# NodeBoard.net
KiCad netlist of a schematic drawn in EAGLE
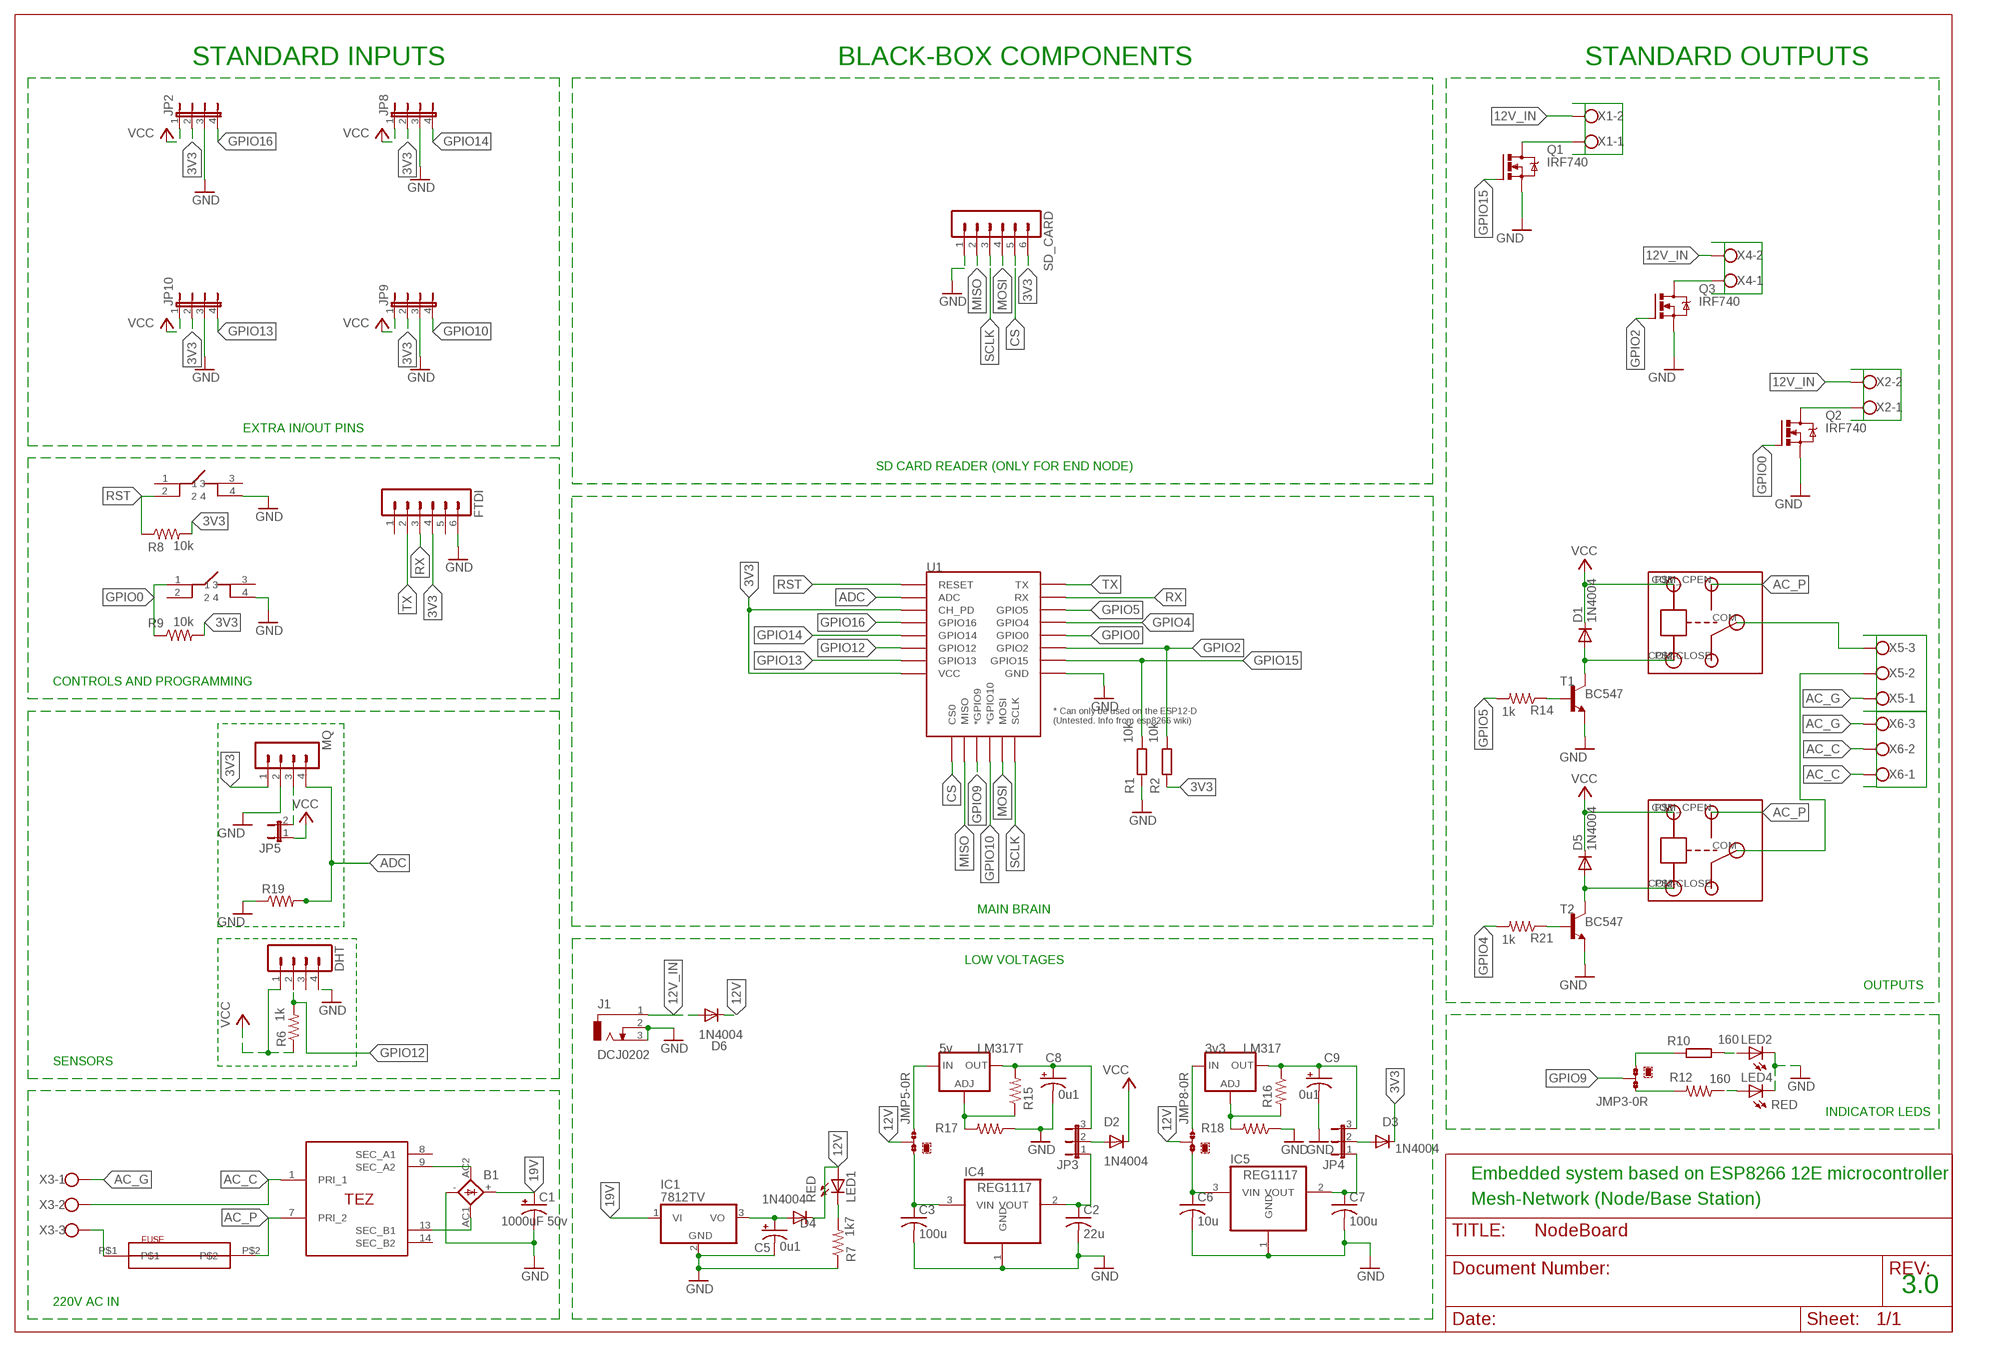
[diagram p0: schematic, sheet 1]

(export (version "E")
  (design (tool "Eeschema 10.0.6"))
  (components
    (comp (ref "B1")
      (value "KBL")
      (footprint "eagle-import:KBL")
      (libsource (lib "eagle-import") (part "KBL"))
    )
    (comp (ref "C1")
      (value "1000uF 50v")
      (footprint "eagle-import:E5-13")
      (libsource (lib "eagle-import") (part "CPOL-USE5-13"))
    )
    (comp (ref "C2")
      (value "22u")
      (footprint "eagle-import:C0805")
      (libsource (lib "eagle-import") (part "C-USC0805"))
    )
    (comp (ref "C3")
      (value "100u")
      (footprint "eagle-import:C0805")
      (libsource (lib "eagle-import") (part "C-USC0805"))
    )
    (comp (ref "C5")
      (value "0u1")
      (footprint "eagle-import:E2,5-6E")
      (libsource (lib "eagle-import") (part "resistor_CPOL-USE2,5-6E"))
    )
    (comp (ref "C6")
      (value "10u")
      (footprint "eagle-import:C0805")
      (libsource (lib "eagle-import") (part "C-USC0805"))
    )
    (comp (ref "C7")
      (value "100u")
      (footprint "eagle-import:C0805")
      (libsource (lib "eagle-import") (part "C-USC0805"))
    )
    (comp (ref "C8")
      (value "0u1")
      (footprint "eagle-import:E2,5-6E")
      (libsource (lib "eagle-import") (part "resistor_CPOL-USE2,5-6E"))
    )
    (comp (ref "C9")
      (value "0u1")
      (footprint "eagle-import:E2,5-6E")
      (libsource (lib "eagle-import") (part "resistor_CPOL-USE2,5-6E"))
    )
    (comp (ref "D1")
      (value "1N4004")
      (footprint "eagle-import:DO41-10")
      (libsource (lib "eagle-import") (part "1N4004"))
    )
    (comp (ref "D2")
      (value "1N4004")
      (footprint "eagle-import:DO41-10")
      (libsource (lib "eagle-import") (part "1N4004"))
    )
    (comp (ref "D3")
      (value "1N4004")
      (footprint "eagle-import:DO41-10")
      (libsource (lib "eagle-import") (part "1N4004"))
    )
    (comp (ref "D4")
      (value "1N4004")
      (footprint "eagle-import:DO41-10")
      (libsource (lib "eagle-import") (part "1N4004"))
    )
    (comp (ref "D5")
      (value "1N4004")
      (footprint "eagle-import:DO41-10")
      (libsource (lib "eagle-import") (part "1N4004"))
    )
    (comp (ref "D6")
      (value "1N4004")
      (footprint "eagle-import:DO41-10")
      (libsource (lib "eagle-import") (part "1N4004"))
    )
    (comp (ref "DHT")
      (value "MA04-1")
      (footprint "eagle-import:MA04-1")
      (libsource (lib "eagle-import") (part "MA04-1"))
    )
    (comp (ref "FTDI")
      (value "MA06-1")
      (footprint "eagle-import:MA06-1")
      (libsource (lib "eagle-import") (part "MA06-1"))
    )
    (comp (ref "IC1")
      (value "7812TV")
      (footprint "eagle-import:TO220V")
      (libsource (lib "eagle-import") (part "78TV12"))
    )
    (comp (ref "IC4")
      (value "REG1117")
      (footprint "eagle-import:SOT223")
      (libsource (lib "eagle-import") (part "REG1117"))
    )
    (comp (ref "IC5")
      (value "REG1117")
      (footprint "eagle-import:SOT223")
      (libsource (lib "eagle-import") (part "REG1117"))
    )
    (comp (ref "J1")
      (value "DCJ0202")
      (footprint "eagle-import:DCJ0202")
      (libsource (lib "eagle-import") (part "DCJ0202"))
    )
    (comp (ref "JMP3")
      (value "0R-JUMPA")
      (footprint "eagle-import:A0R-JMP")
      (libsource (lib "eagle-import") (part "0R-JUMPA"))
    )
    (comp (ref "JMP5")
      (value "0R-JUMPA")
      (footprint "eagle-import:A0R-JMP")
      (libsource (lib "eagle-import") (part "0R-JUMPA"))
    )
    (comp (ref "JMP8")
      (value "0R-JUMPA")
      (footprint "eagle-import:A0R-JMP")
      (libsource (lib "eagle-import") (part "0R-JUMPA"))
    )
    (comp (ref "JP2")
      (value "JP4E")
      (footprint "eagle-import:JP4")
      (libsource (lib "eagle-import") (part "JP4E"))
    )
    (comp (ref "JP3")
      (value "JP2E")
      (footprint "eagle-import:JP2")
      (libsource (lib "eagle-import") (part "JP2E"))
    )
    (comp (ref "JP4")
      (value "JP2E")
      (footprint "eagle-import:JP2")
      (libsource (lib "eagle-import") (part "JP2E"))
    )
    (comp (ref "JP5")
      (value "JP1E")
      (footprint "eagle-import:JP1")
      (libsource (lib "eagle-import") (part "JP1E"))
    )
    (comp (ref "JP8")
      (value "JP4E")
      (footprint "eagle-import:JP4")
      (libsource (lib "eagle-import") (part "JP4E"))
    )
    (comp (ref "JP9")
      (value "JP4E")
      (footprint "eagle-import:JP4")
      (libsource (lib "eagle-import") (part "JP4E"))
    )
    (comp (ref "JP10")
      (value "JP4E")
      (footprint "eagle-import:JP4")
      (libsource (lib "eagle-import") (part "JP4E"))
    )
    (comp (ref "LED1")
      (value "RED")
      (footprint "eagle-import:LED5MM")
      (libsource (lib "eagle-import") (part "led_LED5MM"))
    )
    (comp (ref "LED2")
      (value "LEDCHIPLED_1206")
      (footprint "eagle-import:CHIPLED_1206")
      (libsource (lib "eagle-import") (part "LEDCHIPLED_1206"))
    )
    (comp (ref "LED4")
      (value "RED")
      (footprint "eagle-import:LED5MM")
      (libsource (lib "eagle-import") (part "led_LED5MM"))
    )
    (comp (ref "LM317")
      (value "3v3")
      (footprint "eagle-import:317TS")
      (libsource (lib "eagle-import") (part "LM317TS"))
    )
    (comp (ref "LM317T")
      (value "5v")
      (footprint "eagle-import:317TS")
      (libsource (lib "eagle-import") (part "LM317TS"))
    )
    (comp (ref "MQ")
      (value "MA04-1")
      (footprint "eagle-import:MA04-1")
      (libsource (lib "eagle-import") (part "MA04-1"))
    )
    (comp (ref "Q1")
      (value "IRF740")
      (footprint "eagle-import:TO220BV")
      (libsource (lib "eagle-import") (part "IRF740"))
    )
    (comp (ref "Q2")
      (value "IRF740")
      (footprint "eagle-import:TO220BV")
      (libsource (lib "eagle-import") (part "IRF740"))
    )
    (comp (ref "Q3")
      (value "IRF740")
      (footprint "eagle-import:TO220BV")
      (libsource (lib "eagle-import") (part "IRF740"))
    )
    (comp (ref "R1")
      (value "10k")
      (footprint "eagle-import:R0603")
      (libsource (lib "eagle-import") (part "R-EU_R0603"))
    )
    (comp (ref "R2")
      (value "10k")
      (footprint "eagle-import:R0603")
      (libsource (lib "eagle-import") (part "R-EU_R0603"))
    )
    (comp (ref "R6")
      (value "1k")
      (footprint "eagle-import:0204_7")
      (libsource (lib "eagle-import") (part "R-US_0204/7"))
    )
    (comp (ref "R7")
      (value "1k7")
      (footprint "eagle-import:0204_7")
      (libsource (lib "eagle-import") (part "R-US_0204/7"))
    )
    (comp (ref "R8")
      (value "10k")
      (footprint "eagle-import:0204_7")
      (libsource (lib "eagle-import") (part "R-US_0204/7"))
    )
    (comp (ref "R9")
      (value "10k")
      (footprint "eagle-import:0204_7")
      (libsource (lib "eagle-import") (part "R-US_0204/7"))
    )
    (comp (ref "R10")
      (value "160")
      (footprint "eagle-import:R0603")
      (libsource (lib "eagle-import") (part "R-EU_R0603"))
    )
    (comp (ref "R12")
      (value "160")
      (footprint "eagle-import:0204_7")
      (libsource (lib "eagle-import") (part "R-US_0204/7"))
    )
    (comp (ref "R14")
      (value "1k")
      (footprint "eagle-import:0204_7")
      (libsource (lib "eagle-import") (part "R-US_0204/7"))
    )
    (comp (ref "R15")
      (value "15k")
      (footprint "eagle-import:0204_7")
      (libsource (lib "eagle-import") (part "R-US_0204/7"))
    )
    (comp (ref "R16")
      (value "1k7")
      (footprint "eagle-import:0204_7")
      (libsource (lib "eagle-import") (part "R-US_0204/7"))
    )
    (comp (ref "R17")
      (value "28k")
      (footprint "eagle-import:0204_7")
      (libsource (lib "eagle-import") (part "R-US_0204/7"))
    )
    (comp (ref "R18")
      (value "1k7")
      (footprint "eagle-import:0204_7")
      (libsource (lib "eagle-import") (part "R-US_0204/7"))
    )
    (comp (ref "R19")
      (value "R-US_0204/7")
      (footprint "eagle-import:0204_7")
      (libsource (lib "eagle-import") (part "R-US_0204/7"))
    )
    (comp (ref "R21")
      (value "1k")
      (footprint "eagle-import:0204_7")
      (libsource (lib "eagle-import") (part "R-US_0204/7"))
    )
    (comp (ref "SD_CARD")
      (value "MA06-1")
      (footprint "eagle-import:MA06-1")
      (libsource (lib "eagle-import") (part "MA06-1"))
    )
    (comp (ref "T1")
      (value "BC547")
      (footprint "eagle-import:TO92")
      (libsource (lib "eagle-import") (part "BC547"))
    )
    (comp (ref "T2")
      (value "BC547")
      (footprint "eagle-import:TO92")
      (libsource (lib "eagle-import") (part "BC547"))
    )
    (comp (ref "U$1")
      (value "RELAY")
      (footprint "eagle-import:RELAY")
      (libsource (lib "eagle-import") (part "RELAY"))
    )
    (comp (ref "U$2")
      (value "TEZ_16THROUGH_HOLE")
      (footprint "eagle-import:TEZ_16")
      (libsource (lib "eagle-import") (part "TEZ_16THROUGH_HOLE"))
    )
    (comp (ref "U$3")
      (value "FUSE_24X11THROUGH_HOLE")
      (footprint "eagle-import:FUSE_24X11")
      (libsource (lib "eagle-import") (part "FUSE_24X11THROUGH_HOLE"))
    )
    (comp (ref "U$4")
      (value "RELAY")
      (footprint "eagle-import:RELAY")
      (libsource (lib "eagle-import") (part "RELAY"))
    )
    (comp (ref "U$5")
      (value "TACT_SWITCHTHROUGH_HOLE")
      (footprint "eagle-import:TACT_SWITCH_TH")
      (libsource (lib "eagle-import") (part "TACT_SWITCHTHROUGH_HOLE"))
    )
    (comp (ref "U$6")
      (value "TACT_SWITCHTHROUGH_HOLE")
      (footprint "eagle-import:TACT_SWITCH_TH")
      (libsource (lib "eagle-import") (part "TACT_SWITCHTHROUGH_HOLE"))
    )
    (comp (ref "U1")
      (value "ESP12ESMD")
      (footprint "eagle-import:ESP12E-SMD")
      (libsource (lib "eagle-import") (part "ESP12ESMD"))
    )
    (comp (ref "X1")
      (value "W237-102")
      (footprint "eagle-import:W237-102")
      (fields (field (name "MPN") "237-102"))
      (libsource (lib "eagle-import") (part "W237-102"))
    )
    (comp (ref "X2")
      (value "W237-102")
      (footprint "eagle-import:W237-102")
      (fields (field (name "MPN") "237-102"))
      (libsource (lib "eagle-import") (part "W237-102"))
    )
    (comp (ref "X3")
      (value "W237-103")
      (footprint "eagle-import:W237-103")
      (fields (field (name "MPN") "237-103"))
      (libsource (lib "eagle-import") (part "W237-103"))
    )
    (comp (ref "X4")
      (value "W237-102")
      (footprint "eagle-import:W237-102")
      (fields (field (name "MPN") "237-102"))
      (libsource (lib "eagle-import") (part "W237-102"))
    )
    (comp (ref "X5")
      (value "W237-103")
      (footprint "eagle-import:W237-103")
      (fields (field (name "MPN") "237-103"))
      (libsource (lib "eagle-import") (part "W237-103"))
    )
    (comp (ref "X6")
      (value "W237-103")
      (footprint "eagle-import:W237-103")
      (fields (field (name "MPN") "237-103"))
      (libsource (lib "eagle-import") (part "W237-103"))
    )
  )
  (nets
    (net (code "1") (name "3V3") (class "Default")
      (node (ref "D3") (pin "C") (pinfunction "C_C") (pintype "passive"))
      (node (ref "FTDI") (pin "4") (pinfunction "4_4") (pintype "passive"))
      (node (ref "JP10") (pin "2") (pinfunction "2_2") (pintype "passive"))
      (node (ref "JP2") (pin "2") (pinfunction "2_2") (pintype "passive"))
      (node (ref "JP8") (pin "2") (pinfunction "2_2") (pintype "passive"))
      (node (ref "JP9") (pin "2") (pinfunction "2_2") (pintype "passive"))
      (node (ref "MQ") (pin "1") (pinfunction "1_1") (pintype "passive"))
      (node (ref "R2") (pin "1") (pinfunction "1_1") (pintype "passive"))
      (node (ref "R8") (pin "2") (pinfunction "2_2") (pintype "passive"))
      (node (ref "R9") (pin "2") (pinfunction "2_2") (pintype "passive"))
      (node (ref "SD_CARD") (pin "6") (pinfunction "6_6") (pintype "passive"))
      (node (ref "U1") (pin "CH_PD") (pinfunction "CH_PD_CH_PD") (pintype "bidirectional"))
      (node (ref "U1") (pin "VCC") (pinfunction "VCC_VCC") (pintype "bidirectional"))
    )
    (net (code "2") (name "12V") (class "Default")
      (node (ref "D4") (pin "C") (pinfunction "C_C") (pintype "passive"))
      (node (ref "D6") (pin "C") (pinfunction "C_C") (pintype "passive"))
      (node (ref "JMP5") (pin "2") (pinfunction "2_2") (pintype "passive"))
      (node (ref "JMP8") (pin "2") (pinfunction "2_2") (pintype "passive"))
      (node (ref "LED1") (pin "A") (pinfunction "A_A") (pintype "passive"))
    )
    (net (code "3") (name "12V_IN") (class "Default")
      (node (ref "D6") (pin "A") (pinfunction "A_A") (pintype "passive"))
      (node (ref "J1") (pin "1") (pinfunction "1_1") (pintype "passive"))
      (node (ref "X1") (pin "2") (pinfunction "KL_2") (pintype "passive"))
      (node (ref "X2") (pin "2") (pinfunction "KL_2") (pintype "passive"))
      (node (ref "X4") (pin "2") (pinfunction "KL_2") (pintype "passive"))
    )
    (net (code "4") (name "19V") (class "Default")
      (node (ref "B1") (pin "+") (pinfunction "+_+") (pintype "passive"))
      (node (ref "C1") (pin "+") (pinfunction "+_+") (pintype "passive"))
      (node (ref "IC1") (pin "1") (pinfunction "VI_1") (pintype "input"))
    )
    (net (code "5") (name "AC_C") (class "Default")
      (node (ref "U$2") (pin "1") (pinfunction "PRI_1_1") (pintype "bidirectional"))
      (node (ref "X3") (pin "2") (pinfunction "KL_2") (pintype "passive"))
      (node (ref "X6") (pin "1") (pinfunction "KL_1") (pintype "passive"))
      (node (ref "X6") (pin "2") (pinfunction "KL_2") (pintype "passive"))
    )
    (net (code "6") (name "AC_G") (class "Default")
      (node (ref "X3") (pin "1") (pinfunction "KL_1") (pintype "passive"))
      (node (ref "X5") (pin "1") (pinfunction "KL_1") (pintype "passive"))
      (node (ref "X6") (pin "3") (pinfunction "KL_3") (pintype "passive"))
    )
    (net (code "7") (name "AC_P") (class "Default")
      (node (ref "U$1") (pin "COM_CPEN") (pinfunction "COM-OPEN_COM_CPEN") (pintype "bidirectional"))
      (node (ref "U$2") (pin "7") (pinfunction "PRI_2_7") (pintype "bidirectional"))
      (node (ref "U$3") (pin "P$2") (pinfunction "P$2_P$2") (pintype "bidirectional"))
      (node (ref "U$4") (pin "COM_CPEN") (pinfunction "COM-OPEN_COM_CPEN") (pintype "bidirectional"))
    )
    (net (code "8") (name "ADC") (class "Default")
      (node (ref "MQ") (pin "4") (pinfunction "4_4") (pintype "passive"))
      (node (ref "R19") (pin "2") (pinfunction "2_2") (pintype "passive"))
      (node (ref "U1") (pin "ADC") (pinfunction "ADC_ADC") (pintype "bidirectional"))
    )
    (net (code "9") (name "CS") (class "Default")
      (node (ref "SD_CARD") (pin "5") (pinfunction "5_5") (pintype "passive"))
      (node (ref "U1") (pin "CS0") (pinfunction "CS0_CS0") (pintype "bidirectional"))
    )
    (net (code "10") (name "GND") (class "Default")
      (node (ref "B1") (pin "-") (pinfunction "-_-") (pintype "passive"))
      (node (ref "C1") (pin "-") (pinfunction "-_-") (pintype "passive"))
      (node (ref "C2") (pin "2") (pinfunction "2_2") (pintype "passive"))
      (node (ref "C3") (pin "2") (pinfunction "2_2") (pintype "passive"))
      (node (ref "C5") (pin "-") (pinfunction "-_-") (pintype "passive"))
      (node (ref "C6") (pin "2") (pinfunction "2_2") (pintype "passive"))
      (node (ref "C7") (pin "2") (pinfunction "2_2") (pintype "passive"))
      (node (ref "C8") (pin "-") (pinfunction "-_-") (pintype "passive"))
      (node (ref "C9") (pin "-") (pinfunction "-_-") (pintype "passive"))
      (node (ref "DHT") (pin "4") (pinfunction "4_4") (pintype "passive"))
      (node (ref "FTDI") (pin "6") (pinfunction "6_6") (pintype "passive"))
      (node (ref "IC1") (pin "2") (pinfunction "GND_2") (pintype "passive"))
      (node (ref "IC4") (pin "1") (pinfunction "GND_1") (pintype "power_in"))
      (node (ref "IC5") (pin "1") (pinfunction "GND_1") (pintype "power_in"))
      (node (ref "J1") (pin "2") (pinfunction "2_2") (pintype "passive"))
      (node (ref "J1") (pin "3") (pinfunction "3_3") (pintype "passive"))
      (node (ref "JP10") (pin "3") (pinfunction "3_3") (pintype "passive"))
      (node (ref "JP2") (pin "3") (pinfunction "3_3") (pintype "passive"))
      (node (ref "JP8") (pin "3") (pinfunction "3_3") (pintype "passive"))
      (node (ref "JP9") (pin "3") (pinfunction "3_3") (pintype "passive"))
      (node (ref "LED2") (pin "C") (pinfunction "C_C") (pintype "passive"))
      (node (ref "LED4") (pin "K") (pinfunction "C_K") (pintype "passive"))
      (node (ref "MQ") (pin "2") (pinfunction "2_2") (pintype "passive"))
      (node (ref "Q1") (pin "S") (pinfunction "S_S") (pintype "passive"))
      (node (ref "Q2") (pin "S") (pinfunction "S_S") (pintype "passive"))
      (node (ref "Q3") (pin "S") (pinfunction "S_S") (pintype "passive"))
      (node (ref "R1") (pin "1") (pinfunction "1_1") (pintype "passive"))
      (node (ref "R17") (pin "1") (pinfunction "1_1") (pintype "passive"))
      (node (ref "R18") (pin "1") (pinfunction "1_1") (pintype "passive"))
      (node (ref "R19") (pin "1") (pinfunction "1_1") (pintype "passive"))
      (node (ref "R7") (pin "1") (pinfunction "1_1") (pintype "passive"))
      (node (ref "SD_CARD") (pin "1") (pinfunction "1_1") (pintype "passive"))
      (node (ref "T1") (pin "1") (pinfunction "E_1") (pintype "passive"))
      (node (ref "T2") (pin "1") (pinfunction "E_1") (pintype "passive"))
      (node (ref "U$5") (pin "4") (pinfunction "4_4") (pintype "bidirectional"))
      (node (ref "U$6") (pin "4") (pinfunction "4_4") (pintype "bidirectional"))
      (node (ref "U1") (pin "GND") (pinfunction "GND_GND") (pintype "bidirectional"))
    )
    (net (code "11") (name "GPIO0") (class "Default")
      (node (ref "Q2") (pin "G") (pinfunction "G_G") (pintype "passive"))
      (node (ref "R9") (pin "1") (pinfunction "1_1") (pintype "passive"))
      (node (ref "U$6") (pin "1") (pinfunction "1_1") (pintype "bidirectional"))
      (node (ref "U1") (pin "GPIO0") (pinfunction "GPIO0_GPIO0") (pintype "bidirectional"))
    )
    (net (code "12") (name "GPIO2") (class "Default")
      (node (ref "Q3") (pin "G") (pinfunction "G_G") (pintype "passive"))
      (node (ref "R2") (pin "2") (pinfunction "2_2") (pintype "passive"))
      (node (ref "U1") (pin "GPIO2") (pinfunction "GPIO2_GPIO2") (pintype "bidirectional"))
    )
    (net (code "13") (name "GPIO4") (class "Default")
      (node (ref "R21") (pin "2") (pinfunction "2_2") (pintype "passive"))
      (node (ref "U1") (pin "GPIO4") (pinfunction "GPIO4_GPIO4") (pintype "bidirectional"))
    )
    (net (code "14") (name "GPIO5") (class "Default")
      (node (ref "R14") (pin "2") (pinfunction "2_2") (pintype "passive"))
      (node (ref "U1") (pin "GPIO5") (pinfunction "GPIO5_GPIO5") (pintype "bidirectional"))
    )
    (net (code "15") (name "GPIO9") (class "Default")
      (node (ref "JMP3") (pin "2") (pinfunction "2_2") (pintype "passive"))
      (node (ref "U1") (pin "GPIO9") (pinfunction "*GPIO9_GPIO9") (pintype "bidirectional"))
    )
    (net (code "16") (name "GPIO10") (class "Default")
      (node (ref "JP9") (pin "4") (pinfunction "4_4") (pintype "passive"))
      (node (ref "U1") (pin "GPIO10") (pinfunction "*GPIO10_GPIO10") (pintype "bidirectional"))
    )
    (net (code "17") (name "GPIO12") (class "Default")
      (node (ref "DHT") (pin "2") (pinfunction "2_2") (pintype "passive"))
      (node (ref "R6") (pin "2") (pinfunction "2_2") (pintype "passive"))
      (node (ref "U1") (pin "GPIO12") (pinfunction "GPIO12_GPIO12") (pintype "bidirectional"))
    )
    (net (code "18") (name "GPIO13") (class "Default")
      (node (ref "JP10") (pin "4") (pinfunction "4_4") (pintype "passive"))
      (node (ref "U1") (pin "GPIO13") (pinfunction "GPIO13_GPIO13") (pintype "bidirectional"))
    )
    (net (code "19") (name "GPIO14") (class "Default")
      (node (ref "JP8") (pin "4") (pinfunction "4_4") (pintype "passive"))
      (node (ref "U1") (pin "GPIO14") (pinfunction "GPIO14_GPIO14") (pintype "bidirectional"))
    )
    (net (code "20") (name "GPIO15") (class "Default")
      (node (ref "Q1") (pin "G") (pinfunction "G_G") (pintype "passive"))
      (node (ref "R1") (pin "2") (pinfunction "2_2") (pintype "passive"))
      (node (ref "U1") (pin "GPIO15") (pinfunction "GPIO15_GPIO15") (pintype "bidirectional"))
    )
    (net (code "21") (name "GPIO16") (class "Default")
      (node (ref "JP2") (pin "4") (pinfunction "4_4") (pintype "passive"))
      (node (ref "U1") (pin "GPIO16") (pinfunction "GPIO16_GPIO16") (pintype "bidirectional"))
    )
    (net (code "22") (name "MISO") (class "Default")
      (node (ref "SD_CARD") (pin "2") (pinfunction "2_2") (pintype "passive"))
      (node (ref "U1") (pin "MISO") (pinfunction "MISO_MISO") (pintype "bidirectional"))
    )
    (net (code "23") (name "MOSI") (class "Default")
      (node (ref "SD_CARD") (pin "4") (pinfunction "4_4") (pintype "passive"))
      (node (ref "U1") (pin "MOSI") (pinfunction "MOSI_MOSI") (pintype "bidirectional"))
    )
    (net (code "24") (name "Net-(B1-AC1)") (class "Default")
      (node (ref "B1") (pin "AC2") (pinfunction "AC1_AC2") (pintype "passive"))
      (node (ref "U$2") (pin "9") (pinfunction "SEC_A2_9") (pintype "bidirectional"))
    )
    (net (code "25") (name "Net-(B1-AC2)") (class "Default")
      (node (ref "B1") (pin "AC1") (pinfunction "AC2_AC1") (pintype "passive"))
      (node (ref "U$2") (pin "13") (pinfunction "SEC_B1_13") (pintype "bidirectional"))
    )
    (net (code "26") (name "Net-(D2-PadA)") (class "Default")
      (node (ref "D2") (pin "A") (pinfunction "A_A") (pintype "passive"))
      (node (ref "JP3") (pin "2") (pinfunction "2_2") (pintype "passive"))
    )
    (net (code "27") (name "Net-(D3-PadA)") (class "Default")
      (node (ref "D3") (pin "A") (pinfunction "A_A") (pintype "passive"))
      (node (ref "JP4") (pin "2") (pinfunction "2_2") (pintype "passive"))
    )
    (net (code "28") (name "Net-(IC1-VO)") (class "Default")
      (node (ref "C5") (pin "+") (pinfunction "+_+") (pintype "passive"))
      (node (ref "D4") (pin "A") (pinfunction "A_A") (pintype "passive"))
      (node (ref "IC1") (pin "3") (pinfunction "VO_3") (pintype "passive"))
    )
    (net (code "29") (name "Net-(IC4-VIN)") (class "Default")
      (node (ref "C3") (pin "1") (pinfunction "1_1") (pintype "passive"))
      (node (ref "IC4") (pin "3") (pinfunction "VIN_3") (pintype "input"))
      (node (ref "JMP5") (pin "1") (pinfunction "1_1") (pintype "passive"))
    )
    (net (code "30") (name "Net-(IC4-VOUT)") (class "Default")
      (node (ref "C2") (pin "1") (pinfunction "1_1") (pintype "passive"))
      (node (ref "IC4") (pin "2") (pinfunction "VOUT_2") (pintype "output"))
      (node (ref "JP3") (pin "1") (pinfunction "1_1") (pintype "passive"))
    )
    (net (code "31") (name "Net-(IC5-VIN)") (class "Default")
      (node (ref "C6") (pin "1") (pinfunction "1_1") (pintype "passive"))
      (node (ref "IC5") (pin "3") (pinfunction "VIN_3") (pintype "input"))
      (node (ref "JMP8") (pin "1") (pinfunction "1_1") (pintype "passive"))
    )
    (net (code "32") (name "Net-(IC5-VOUT)") (class "Default")
      (node (ref "C7") (pin "1") (pinfunction "1_1") (pintype "passive"))
      (node (ref "IC5") (pin "2") (pinfunction "VOUT_2") (pintype "output"))
      (node (ref "JP4") (pin "1") (pinfunction "1_1") (pintype "passive"))
    )
    (net (code "33") (name "Net-(JMP3-Pad1)") (class "Default")
      (node (ref "JMP3") (pin "1") (pinfunction "1_1") (pintype "passive"))
      (node (ref "R12") (pin "2") (pinfunction "2_2") (pintype "passive"))
    )
    (net (code "34") (name "Net-(JMP3-Pad3)") (class "Default")
      (node (ref "JMP3") (pin "3") (pinfunction "3_3") (pintype "passive"))
      (node (ref "R10") (pin "1") (pinfunction "1_1") (pintype "passive"))
    )
    (net (code "35") (name "Net-(JP5-Pad2)") (class "Default")
      (node (ref "JP5") (pin "2") (pinfunction "2_2") (pintype "passive"))
      (node (ref "MQ") (pin "3") (pinfunction "3_3") (pintype "passive"))
    )
    (net (code "36") (name "Net-(LED1-C)") (class "Default")
      (node (ref "LED1") (pin "K") (pinfunction "C_K") (pintype "passive"))
      (node (ref "R7") (pin "2") (pinfunction "2_2") (pintype "passive"))
    )
    (net (code "37") (name "Net-(LED2-PadA)") (class "Default")
      (node (ref "LED2") (pin "A") (pinfunction "A_A") (pintype "passive"))
      (node (ref "R10") (pin "2") (pinfunction "2_2") (pintype "passive"))
    )
    (net (code "38") (name "Net-(LED4-PadA)") (class "Default")
      (node (ref "LED4") (pin "A") (pinfunction "A_A") (pintype "passive"))
      (node (ref "R12") (pin "1") (pinfunction "1_1") (pintype "passive"))
    )
    (net (code "39") (name "Net-(LM317-ADJ)") (class "Default")
      (node (ref "LM317") (pin "1") (pinfunction "ADJ_1") (pintype "input"))
      (node (ref "R16") (pin "2") (pinfunction "2_2") (pintype "passive"))
      (node (ref "R18") (pin "2") (pinfunction "2_2") (pintype "passive"))
    )
    (net (code "40") (name "Net-(LM317-IN)") (class "Default")
      (node (ref "JMP8") (pin "3") (pinfunction "3_3") (pintype "passive"))
      (node (ref "LM317") (pin "3") (pinfunction "IN_3") (pintype "input"))
    )
    (net (code "41") (name "Net-(LM317-OUT)") (class "Default")
      (node (ref "C9") (pin "+") (pinfunction "+_+") (pintype "passive"))
      (node (ref "JP4") (pin "3") (pinfunction "3_3") (pintype "passive"))
      (node (ref "LM317") (pin "2") (pinfunction "OUT_2") (pintype "passive"))
      (node (ref "R16") (pin "1") (pinfunction "1_1") (pintype "passive"))
    )
    (net (code "42") (name "Net-(LM317T-ADJ)") (class "Default")
      (node (ref "LM317T") (pin "1") (pinfunction "ADJ_1") (pintype "input"))
      (node (ref "R15") (pin "1") (pinfunction "1_1") (pintype "passive"))
      (node (ref "R17") (pin "2") (pinfunction "2_2") (pintype "passive"))
    )
    (net (code "43") (name "Net-(LM317T-IN)") (class "Default")
      (node (ref "JMP5") (pin "3") (pinfunction "3_3") (pintype "passive"))
      (node (ref "LM317T") (pin "3") (pinfunction "IN_3") (pintype "input"))
    )
    (net (code "44") (name "Net-(LM317T-OUT)") (class "Default")
      (node (ref "C8") (pin "+") (pinfunction "+_+") (pintype "passive"))
      (node (ref "JP3") (pin "3") (pinfunction "3_3") (pintype "passive"))
      (node (ref "LM317T") (pin "2") (pinfunction "OUT_2") (pintype "passive"))
      (node (ref "R15") (pin "2") (pinfunction "2_2") (pintype "passive"))
    )
    (net (code "45") (name "Net-(T1-B)") (class "Default")
      (node (ref "R14") (pin "1") (pinfunction "1_1") (pintype "passive"))
      (node (ref "T1") (pin "2") (pinfunction "B_2") (pintype "passive"))
    )
    (net (code "46") (name "Net-(T1-C)") (class "Default")
      (node (ref "D1") (pin "A") (pinfunction "A_A") (pintype "passive"))
      (node (ref "T1") (pin "3") (pinfunction "C_3") (pintype "passive"))
      (node (ref "U$1") (pin "P$2") (pinfunction "GND_P$2") (pintype "bidirectional"))
    )
    (net (code "47") (name "Net-(T2-B)") (class "Default")
      (node (ref "R21") (pin "1") (pinfunction "1_1") (pintype "passive"))
      (node (ref "T2") (pin "2") (pinfunction "B_2") (pintype "passive"))
    )
    (net (code "48") (name "Net-(T2-C)") (class "Default")
      (node (ref "D5") (pin "A") (pinfunction "A_A") (pintype "passive"))
      (node (ref "T2") (pin "3") (pinfunction "C_3") (pintype "passive"))
      (node (ref "U$4") (pin "P$2") (pinfunction "GND_P$2") (pintype "bidirectional"))
    )
    (net (code "49") (name "Net-(X1A-KL)") (class "Default")
      (node (ref "Q1") (pin "D") (pinfunction "D_D") (pintype "passive"))
      (node (ref "X1") (pin "1") (pinfunction "KL_1") (pintype "passive"))
    )
    (net (code "50") (name "Net-(X2A-KL)") (class "Default")
      (node (ref "Q2") (pin "D") (pinfunction "D_D") (pintype "passive"))
      (node (ref "X2") (pin "1") (pinfunction "KL_1") (pintype "passive"))
    )
    (net (code "51") (name "Net-(X3C-KL)") (class "Default")
      (node (ref "U$3") (pin "P$1") (pinfunction "P$1_P$1") (pintype "bidirectional"))
      (node (ref "X3") (pin "3") (pinfunction "KL_3") (pintype "passive"))
    )
    (net (code "52") (name "Net-(X4A-KL)") (class "Default")
      (node (ref "Q3") (pin "D") (pinfunction "D_D") (pintype "passive"))
      (node (ref "X4") (pin "1") (pinfunction "KL_1") (pintype "passive"))
    )
    (net (code "53") (name "Net-(X5B-KL)") (class "Default")
      (node (ref "U$4") (pin "COM") (pinfunction "COM_COM") (pintype "bidirectional"))
      (node (ref "X5") (pin "2") (pinfunction "KL_2") (pintype "passive"))
    )
    (net (code "54") (name "Net-(X5C-KL)") (class "Default")
      (node (ref "U$1") (pin "COM") (pinfunction "COM_COM") (pintype "bidirectional"))
      (node (ref "X5") (pin "3") (pinfunction "KL_3") (pintype "passive"))
    )
    (net (code "55") (name "RST") (class "Default")
      (node (ref "R8") (pin "1") (pinfunction "1_1") (pintype "passive"))
      (node (ref "U$5") (pin "2") (pinfunction "2_2") (pintype "bidirectional"))
      (node (ref "U1") (pin "RESET") (pinfunction "RESET_RESET") (pintype "bidirectional"))
    )
    (net (code "56") (name "RX") (class "Default")
      (node (ref "FTDI") (pin "3") (pinfunction "3_3") (pintype "passive"))
      (node (ref "U1") (pin "RXD0") (pinfunction "RX_RXD0") (pintype "bidirectional"))
    )
    (net (code "57") (name "SCLK") (class "Default")
      (node (ref "SD_CARD") (pin "3") (pinfunction "3_3") (pintype "passive"))
      (node (ref "U1") (pin "SCLK") (pinfunction "SCLK_SCLK") (pintype "bidirectional"))
    )
    (net (code "58") (name "TX") (class "Default")
      (node (ref "FTDI") (pin "2") (pinfunction "2_2") (pintype "passive"))
      (node (ref "U1") (pin "TXD0") (pinfunction "TX_TXD0") (pintype "bidirectional"))
    )
    (net (code "59") (name "VCC") (class "Default")
      (node (ref "D1") (pin "C") (pinfunction "C_C") (pintype "passive"))
      (node (ref "D2") (pin "C") (pinfunction "C_C") (pintype "passive"))
      (node (ref "D5") (pin "C") (pinfunction "C_C") (pintype "passive"))
      (node (ref "DHT") (pin "1") (pinfunction "1_1") (pintype "passive"))
      (node (ref "JP10") (pin "1") (pinfunction "1_1") (pintype "passive"))
      (node (ref "JP2") (pin "1") (pinfunction "1_1") (pintype "passive"))
      (node (ref "JP5") (pin "1") (pinfunction "1_1") (pintype "passive"))
      (node (ref "JP8") (pin "1") (pinfunction "1_1") (pintype "passive"))
      (node (ref "JP9") (pin "1") (pinfunction "1_1") (pintype "passive"))
      (node (ref "R6") (pin "1") (pinfunction "1_1") (pintype "passive"))
      (node (ref "U$1") (pin "P$1") (pinfunction "IN_P$1") (pintype "bidirectional"))
      (node (ref "U$4") (pin "P$1") (pinfunction "IN_P$1") (pintype "bidirectional"))
    )
    (net (code "60") (name "unconnected-(DHT-Pad3)") (class "Default")
      (node (ref "DHT") (pin "3") (pinfunction "3_3") (pintype "passive"))
    )
    (net (code "61") (name "unconnected-(FTDI-Pad1)") (class "Default")
      (node (ref "FTDI") (pin "1") (pinfunction "1_1") (pintype "passive"))
    )
    (net (code "62") (name "unconnected-(FTDI-Pad5)") (class "Default")
      (node (ref "FTDI") (pin "5") (pinfunction "5_5") (pintype "passive"))
    )
    (net (code "63") (name "unconnected-(U$1-PadCOM-CLOSE)") (class "Default")
      (node (ref "U$1") (pin "COM-CLOSE") (pinfunction "COM-CLOSE_COM-CLOSE") (pintype "bidirectional"))
    )
    (net (code "64") (name "unconnected-(U$2-SEC_A1-Pad8)") (class "Default")
      (node (ref "U$2") (pin "8") (pinfunction "SEC_A1_8") (pintype "bidirectional"))
    )
    (net (code "65") (name "unconnected-(U$2-SEC_B2-Pad14)") (class "Default")
      (node (ref "U$2") (pin "14") (pinfunction "SEC_B2_14") (pintype "bidirectional"))
    )
    (net (code "66") (name "unconnected-(U$4-PadCOM-CLOSE)") (class "Default")
      (node (ref "U$4") (pin "COM-CLOSE") (pinfunction "COM-CLOSE_COM-CLOSE") (pintype "bidirectional"))
    )
    (net (code "67") (name "unconnected-(U$5-Pad1)") (class "Default")
      (node (ref "U$5") (pin "1") (pinfunction "1_1") (pintype "bidirectional"))
    )
    (net (code "68") (name "unconnected-(U$5-Pad3)") (class "Default")
      (node (ref "U$5") (pin "3") (pinfunction "3_3") (pintype "bidirectional"))
    )
    (net (code "69") (name "unconnected-(U$6-Pad2)") (class "Default")
      (node (ref "U$6") (pin "2") (pinfunction "2_2") (pintype "bidirectional"))
    )
    (net (code "70") (name "unconnected-(U$6-Pad3)") (class "Default")
      (node (ref "U$6") (pin "3") (pinfunction "3_3") (pintype "bidirectional"))
    )
  )
)
